# ME433_Spring2017.net
KiCad netlist of a schematic drawn in EAGLE
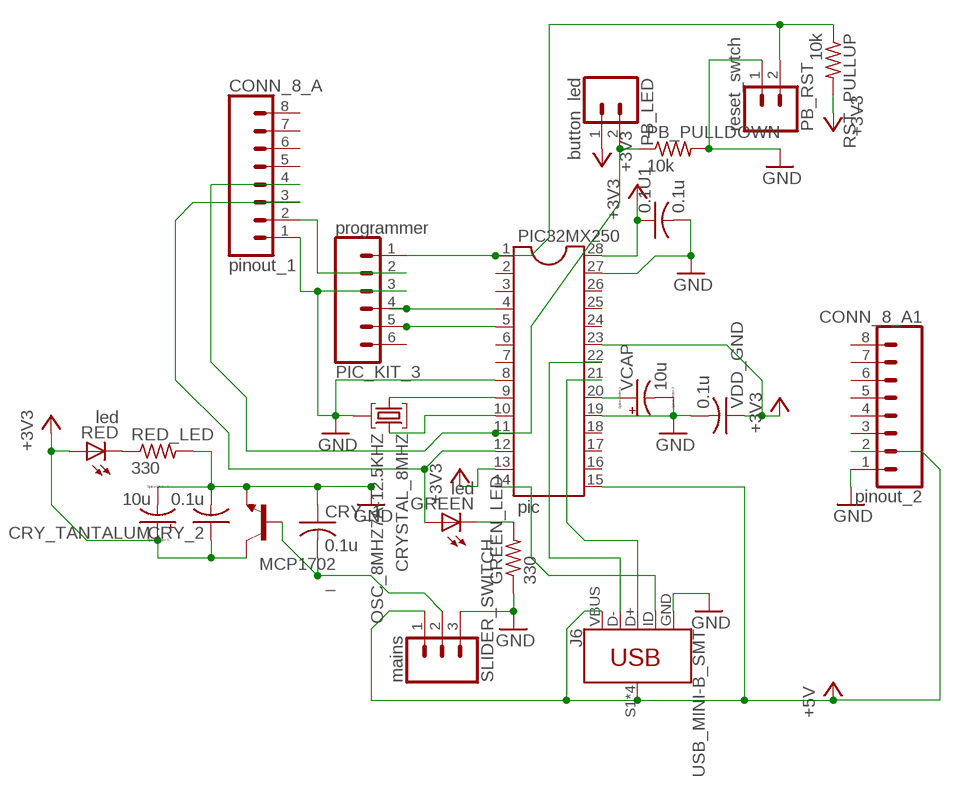
[diagram p0: schematic, sheet 1]

(export (version "E")
  (design (tool "Eeschema 10.0.6"))
  (components
    (comp (ref "0.1U1")
      (value "0.1u")
      (footprint "eagle-import:C025-025X050")
      (libsource (lib "eagle-import") (part "C-US025-025X050"))
    )
    (comp (ref "CONN_8_A")
      (value "pinout_1")
      (footprint "eagle-import:1X08")
      (libsource (lib "eagle-import") (part "CONN_08{dblquote}"))
    )
    (comp (ref "CONN_8_A1")
      (value "pinout_2")
      (footprint "eagle-import:1X08")
      (libsource (lib "eagle-import") (part "CONN_08{dblquote}"))
    )
    (comp (ref "CRYSTAL_8MHZ")
      (value "OSC_8MHZ7A-12.5KHZ")
      (footprint "eagle-import:HC49U")
      (libsource (lib "eagle-import") (part "OSC_8MHZ7A-12.5KHZ"))
    )
    (comp (ref "CRY_1")
      (value "0.1u")
      (footprint "eagle-import:C025-025X050")
      (libsource (lib "eagle-import") (part "C-US025-025X050"))
    )
    (comp (ref "CRY_2")
      (value "0.1u")
      (footprint "eagle-import:C025-025X050")
      (libsource (lib "eagle-import") (part "C-US025-025X050"))
    )
    (comp (ref "CRY_TANTALUM")
      (value "10u")
      (footprint "eagle-import:B45181B")
      (libsource (lib "eagle-import") (part "CPOL-USB45181B"))
    )
    (comp (ref "GREEN")
      (value "led")
      (footprint "eagle-import:SFH482")
      (libsource (lib "eagle-import") (part "LEDSFH482"))
    )
    (comp (ref "GREEN_LED")
      (value "330")
      (footprint "eagle-import:0204_7")
      (libsource (lib "eagle-import") (part "R-US_0204/7"))
    )
    (comp (ref "J6")
      (value "USB_MINI-B_SMT")
      (footprint "eagle-import:USB-MINIB")
      (libsource (lib "eagle-import") (part "USB_MINI-B_SMT"))
    )
    (comp (ref "PB_LED")
      (value "button_led")
      (footprint "eagle-import:BUTTONS")
      (libsource (lib "eagle-import") (part "BUTTONS"))
    )
    (comp (ref "PB_PULLDOWN")
      (value "10k")
      (footprint "eagle-import:0204_7")
      (libsource (lib "eagle-import") (part "R-US_0204/7"))
    )
    (comp (ref "PB_RST")
      (value "reset_swtch")
      (footprint "eagle-import:BUTTONS")
      (libsource (lib "eagle-import") (part "BUTTONS"))
    )
    (comp (ref "PIC32MX250")
      (value "pic")
      (footprint "eagle-import:PIC")
      (libsource (lib "eagle-import") (part "PIC-3"))
    )
    (comp (ref "PIC_KIT_3")
      (value "programmer")
      (footprint "eagle-import:1X06_NO_SILK")
      (libsource (lib "eagle-import") (part "PICKIT3NO_SILK_FEMALE_PTH"))
    )
    (comp (ref "RED")
      (value "led")
      (footprint "eagle-import:SFH482")
      (libsource (lib "eagle-import") (part "LEDSFH482"))
    )
    (comp (ref "RED_LED")
      (value "330")
      (footprint "eagle-import:0204_7")
      (libsource (lib "eagle-import") (part "R-US_0204/7"))
    )
    (comp (ref "RST_PULLUP")
      (value "10k")
      (footprint "eagle-import:0204_7")
      (libsource (lib "eagle-import") (part "R-US_0204/7"))
    )
    (comp (ref "SLIDER_SWITCH")
      (value "mains")
      (footprint "eagle-import:SLIDER_SWITCH_1MM")
      (libsource (lib "eagle-import") (part "SLIDER_SWITCH"))
    )
    (comp (ref "VCAP")
      (value "10u")
      (footprint "eagle-import:B45181B")
      (libsource (lib "eagle-import") (part "CPOL-USB45181B"))
    )
    (comp (ref "VDD_GND")
      (value "0.1u")
      (footprint "eagle-import:C025-025X050")
      (libsource (lib "eagle-import") (part "C-US025-025X050"))
    )
    (comp (ref "_")
      (value "MCP1702")
      (footprint "eagle-import:MCP1702")
      (libsource (lib "eagle-import") (part "MCP1702"))
    )
  )
  (nets
    (net (code "1") (name "+3V3") (class "Default")
      (node (ref "0.1U1") (pin "1") (pinfunction "1_1") (pintype "passive"))
      (node (ref "CRY_2") (pin "1") (pinfunction "1_1") (pintype "passive"))
      (node (ref "CRY_TANTALUM") (pin "+") (pinfunction "+_+") (pintype "passive"))
      (node (ref "PB_LED") (pin "1") (pinfunction "1_1") (pintype "passive"))
      (node (ref "PIC32MX250") (pin "13") (pinfunction "13_13") (pintype "passive"))
      (node (ref "PIC32MX250") (pin "23") (pinfunction "23_23") (pintype "passive"))
      (node (ref "PIC32MX250") (pin "28") (pinfunction "28_28") (pintype "passive"))
      (node (ref "RED") (pin "A") (pinfunction "A_A") (pintype "passive"))
      (node (ref "RST_PULLUP") (pin "2") (pinfunction "2_2") (pintype "passive"))
      (node (ref "VDD_GND") (pin "1") (pinfunction "1_1") (pintype "passive"))
      (node (ref "_") (pin "C") (pinfunction "C_C") (pintype "passive"))
    )
    (net (code "2") (name "+5V") (class "Default")
      (node (ref "CONN_8_A1") (pin "2") (pinfunction "2_2") (pintype "passive"))
      (node (ref "J6") (pin "S1") (pinfunction "SHIELD_S1") (pintype "bidirectional"))
      (node (ref "J6") (pin "S2") (pinfunction "SHIELD_S2") (pintype "bidirectional"))
      (node (ref "J6") (pin "S3") (pinfunction "SHIELD_S3") (pintype "bidirectional"))
      (node (ref "J6") (pin "S4") (pinfunction "SHIELD_S4") (pintype "bidirectional"))
      (node (ref "J6") (pin "VBUS") (pinfunction "VBUS_VBUS") (pintype "power_in"))
      (node (ref "PIC32MX250") (pin "15") (pinfunction "15_15") (pintype "passive"))
      (node (ref "SLIDER_SWITCH") (pin "1") (pinfunction "1_1") (pintype "passive"))
    )
    (net (code "3") (name "GND") (class "Default")
      (node (ref "0.1U1") (pin "2") (pinfunction "2_2") (pintype "passive"))
      (node (ref "CONN_8_A") (pin "1") (pinfunction "1_1") (pintype "passive"))
      (node (ref "CONN_8_A1") (pin "1") (pinfunction "1_1") (pintype "passive"))
      (node (ref "CRYSTAL_8MHZ") (pin "2") (pinfunction "2_2") (pintype "passive"))
      (node (ref "CRY_1") (pin "1") (pinfunction "1_1") (pintype "passive"))
      (node (ref "CRY_2") (pin "2") (pinfunction "2_2") (pintype "passive"))
      (node (ref "CRY_TANTALUM") (pin "-") (pinfunction "-_-") (pintype "passive"))
      (node (ref "GREEN_LED") (pin "1") (pinfunction "1_1") (pintype "passive"))
      (node (ref "J6") (pin "GND") (pinfunction "GND_GND") (pintype "power_in"))
      (node (ref "PB_PULLDOWN") (pin "2") (pinfunction "2_2") (pintype "passive"))
      (node (ref "PB_RST") (pin "1") (pinfunction "1_1") (pintype "passive"))
      (node (ref "PIC32MX250") (pin "19") (pinfunction "19_19") (pintype "passive"))
      (node (ref "PIC32MX250") (pin "27") (pinfunction "27_27") (pintype "passive"))
      (node (ref "PIC32MX250") (pin "8") (pinfunction "8_8") (pintype "passive"))
      (node (ref "PIC_KIT_3") (pin "3") (pinfunction "3_3") (pintype "passive"))
      (node (ref "RED_LED") (pin "2") (pinfunction "2_2") (pintype "passive"))
      (node (ref "SLIDER_SWITCH") (pin "3") (pinfunction "3_3") (pintype "passive"))
      (node (ref "VCAP") (pin "-") (pinfunction "-_-") (pintype "passive"))
      (node (ref "VDD_GND") (pin "2") (pinfunction "2_2") (pintype "passive"))
      (node (ref "_") (pin "E") (pinfunction "E_E") (pintype "passive"))
    )
    (net (code "4") (name "Net-(CONN_8_A-Pad2)") (class "Default")
      (node (ref "CONN_8_A") (pin "2") (pinfunction "2_2") (pintype "passive"))
      (node (ref "PIC_KIT_3") (pin "2") (pinfunction "2_2") (pintype "passive"))
    )
    (net (code "5") (name "Net-(CONN_8_A-Pad3)") (class "Default")
      (node (ref "CONN_8_A") (pin "3") (pinfunction "3_3") (pintype "passive"))
      (node (ref "GREEN") (pin "A") (pinfunction "A_A") (pintype "passive"))
      (node (ref "PIC32MX250") (pin "12") (pinfunction "12_12") (pintype "passive"))
    )
    (net (code "6") (name "Net-(CONN_8_A-Pad4)") (class "Default")
      (node (ref "CONN_8_A") (pin "4") (pinfunction "4_4") (pintype "passive"))
      (node (ref "PB_LED") (pin "2") (pinfunction "2_2") (pintype "passive"))
      (node (ref "PB_PULLDOWN") (pin "1") (pinfunction "1_1") (pintype "passive"))
      (node (ref "PIC32MX250") (pin "11") (pinfunction "11_11") (pintype "passive"))
    )
    (net (code "7") (name "Net-(CRYSTAL_8MHZ-Pad1)") (class "Default")
      (node (ref "CRYSTAL_8MHZ") (pin "1") (pinfunction "1_1") (pintype "passive"))
      (node (ref "PIC32MX250") (pin "9") (pinfunction "9_9") (pintype "passive"))
    )
    (net (code "8") (name "Net-(CRYSTAL_8MHZ-Pad3)") (class "Default")
      (node (ref "CRYSTAL_8MHZ") (pin "3") (pinfunction "3_3") (pintype "passive"))
      (node (ref "PIC32MX250") (pin "10") (pinfunction "10_10") (pintype "passive"))
    )
    (net (code "9") (name "Net-(CRY_1-Pad2)") (class "Default")
      (node (ref "CRY_1") (pin "2") (pinfunction "2_2") (pintype "passive"))
      (node (ref "SLIDER_SWITCH") (pin "2") (pinfunction "2_2") (pintype "passive"))
      (node (ref "_") (pin "B") (pinfunction "B_B") (pintype "passive"))
    )
    (net (code "10") (name "Net-(GREEN-C)") (class "Default")
      (node (ref "GREEN") (pin "K") (pinfunction "C_K") (pintype "passive"))
      (node (ref "GREEN_LED") (pin "2") (pinfunction "2_2") (pintype "passive"))
    )
    (net (code "11") (name "Net-(J6-PadD+)") (class "Default")
      (node (ref "J6") (pin "D+") (pinfunction "D+_D+") (pintype "bidirectional"))
      (node (ref "PIC32MX250") (pin "21") (pinfunction "21_21") (pintype "passive"))
    )
    (net (code "12") (name "Net-(J6-PadD-)") (class "Default")
      (node (ref "J6") (pin "D-") (pinfunction "D-_D-") (pintype "bidirectional"))
      (node (ref "PIC32MX250") (pin "22") (pinfunction "22_22") (pintype "passive"))
    )
    (net (code "13") (name "Net-(J6-PadID)") (class "Default")
      (node (ref "J6") (pin "ID") (pinfunction "ID_ID") (pintype "bidirectional"))
      (node (ref "PIC32MX250") (pin "14") (pinfunction "14_14") (pintype "passive"))
    )
    (net (code "14") (name "Net-(PB_RST-Pad2)") (class "Default")
      (node (ref "PB_RST") (pin "2") (pinfunction "2_2") (pintype "passive"))
      (node (ref "PIC32MX250") (pin "1") (pinfunction "1_1") (pintype "passive"))
      (node (ref "PIC_KIT_3") (pin "1") (pinfunction "1_1") (pintype "passive"))
      (node (ref "RST_PULLUP") (pin "1") (pinfunction "1_1") (pintype "passive"))
    )
    (net (code "15") (name "Net-(PIC32MX250-Pad4)") (class "Default")
      (node (ref "PIC32MX250") (pin "4") (pinfunction "4_4") (pintype "passive"))
      (node (ref "PIC_KIT_3") (pin "4") (pinfunction "4_4") (pintype "passive"))
    )
    (net (code "16") (name "Net-(PIC32MX250-Pad5)") (class "Default")
      (node (ref "PIC32MX250") (pin "5") (pinfunction "5_5") (pintype "passive"))
      (node (ref "PIC_KIT_3") (pin "5") (pinfunction "5_5") (pintype "passive"))
    )
    (net (code "17") (name "Net-(PIC32MX250-Pad20)") (class "Default")
      (node (ref "PIC32MX250") (pin "20") (pinfunction "20_20") (pintype "passive"))
      (node (ref "VCAP") (pin "+") (pinfunction "+_+") (pintype "passive"))
    )
    (net (code "18") (name "Net-(RED-C)") (class "Default")
      (node (ref "RED") (pin "K") (pinfunction "C_K") (pintype "passive"))
      (node (ref "RED_LED") (pin "1") (pinfunction "1_1") (pintype "passive"))
    )
    (net (code "19") (name "unconnected-(CONN_8_A-Pad5)") (class "Default")
      (node (ref "CONN_8_A") (pin "5") (pinfunction "5_5") (pintype "passive"))
    )
    (net (code "20") (name "unconnected-(CONN_8_A-Pad6)") (class "Default")
      (node (ref "CONN_8_A") (pin "6") (pinfunction "6_6") (pintype "passive"))
    )
    (net (code "21") (name "unconnected-(CONN_8_A-Pad7)") (class "Default")
      (node (ref "CONN_8_A") (pin "7") (pinfunction "7_7") (pintype "passive"))
    )
    (net (code "22") (name "unconnected-(CONN_8_A-Pad8)") (class "Default")
      (node (ref "CONN_8_A") (pin "8") (pinfunction "8_8") (pintype "passive"))
    )
    (net (code "23") (name "unconnected-(CONN_8_A1-Pad3)") (class "Default")
      (node (ref "CONN_8_A1") (pin "3") (pinfunction "3_3") (pintype "passive"))
    )
    (net (code "24") (name "unconnected-(CONN_8_A1-Pad4)") (class "Default")
      (node (ref "CONN_8_A1") (pin "4") (pinfunction "4_4") (pintype "passive"))
    )
    (net (code "25") (name "unconnected-(CONN_8_A1-Pad5)") (class "Default")
      (node (ref "CONN_8_A1") (pin "5") (pinfunction "5_5") (pintype "passive"))
    )
    (net (code "26") (name "unconnected-(CONN_8_A1-Pad6)") (class "Default")
      (node (ref "CONN_8_A1") (pin "6") (pinfunction "6_6") (pintype "passive"))
    )
    (net (code "27") (name "unconnected-(CONN_8_A1-Pad7)") (class "Default")
      (node (ref "CONN_8_A1") (pin "7") (pinfunction "7_7") (pintype "passive"))
    )
    (net (code "28") (name "unconnected-(CONN_8_A1-Pad8)") (class "Default")
      (node (ref "CONN_8_A1") (pin "8") (pinfunction "8_8") (pintype "passive"))
    )
    (net (code "29") (name "unconnected-(PIC32MX250-Pad2)") (class "Default")
      (node (ref "PIC32MX250") (pin "2") (pinfunction "2_2") (pintype "passive"))
    )
    (net (code "30") (name "unconnected-(PIC32MX250-Pad3)") (class "Default")
      (node (ref "PIC32MX250") (pin "3") (pinfunction "3_3") (pintype "passive"))
    )
    (net (code "31") (name "unconnected-(PIC32MX250-Pad6)") (class "Default")
      (node (ref "PIC32MX250") (pin "6") (pinfunction "6_6") (pintype "passive"))
    )
    (net (code "32") (name "unconnected-(PIC32MX250-Pad7)") (class "Default")
      (node (ref "PIC32MX250") (pin "7") (pinfunction "7_7") (pintype "passive"))
    )
    (net (code "33") (name "unconnected-(PIC32MX250-Pad16)") (class "Default")
      (node (ref "PIC32MX250") (pin "16") (pinfunction "16_16") (pintype "passive"))
    )
    (net (code "34") (name "unconnected-(PIC32MX250-Pad17)") (class "Default")
      (node (ref "PIC32MX250") (pin "17") (pinfunction "17_17") (pintype "passive"))
    )
    (net (code "35") (name "unconnected-(PIC32MX250-Pad18)") (class "Default")
      (node (ref "PIC32MX250") (pin "18") (pinfunction "18_18") (pintype "passive"))
    )
    (net (code "36") (name "unconnected-(PIC32MX250-Pad24)") (class "Default")
      (node (ref "PIC32MX250") (pin "24") (pinfunction "24_24") (pintype "passive"))
    )
    (net (code "37") (name "unconnected-(PIC32MX250-Pad25)") (class "Default")
      (node (ref "PIC32MX250") (pin "25") (pinfunction "25_25") (pintype "passive"))
    )
    (net (code "38") (name "unconnected-(PIC32MX250-Pad26)") (class "Default")
      (node (ref "PIC32MX250") (pin "26") (pinfunction "26_26") (pintype "passive"))
    )
    (net (code "39") (name "unconnected-(PIC_KIT_3-Pad6)") (class "Default")
      (node (ref "PIC_KIT_3") (pin "6") (pinfunction "6_6") (pintype "passive"))
    )
  )
)
